# AQM2a.net
KiCad netlist of a schematic drawn in EasyEDA Pro
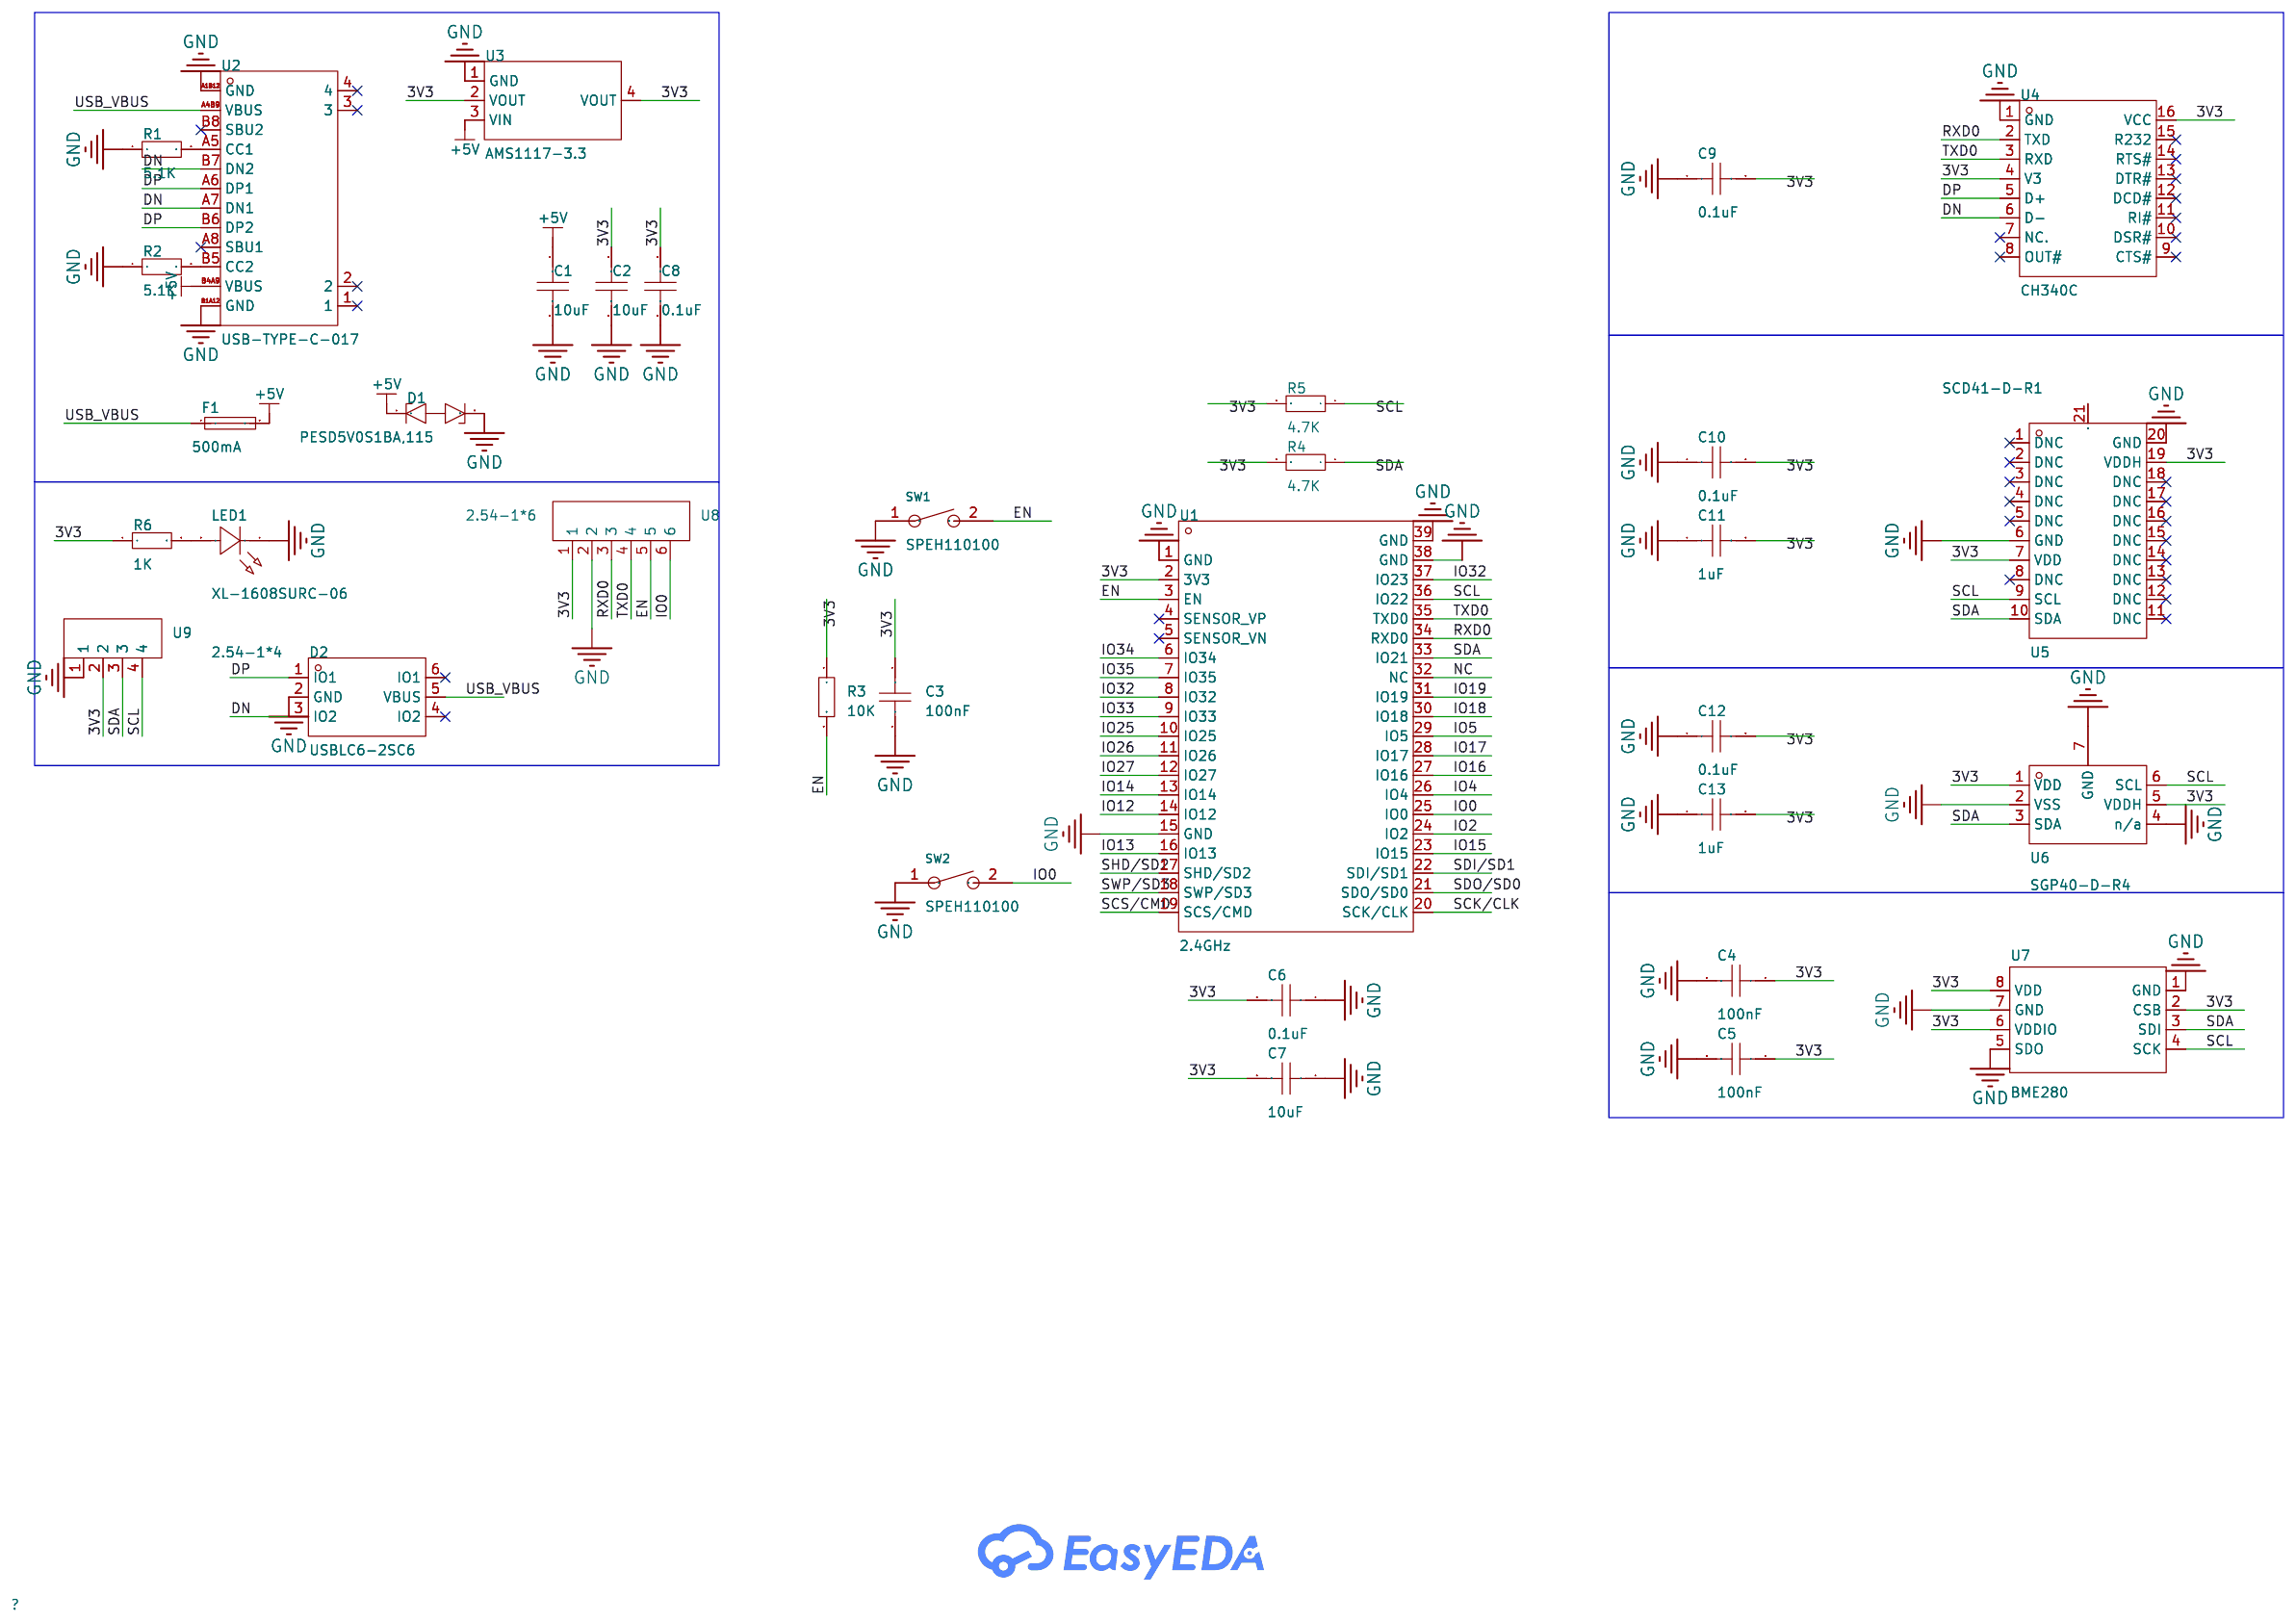
[diagram p0: schematic sheet]

(export (version "E")
  (design (tool "Eeschema 10.0.6"))
  (components
    (comp (ref "C1")
      (value "10uF")
      (footprint "easyedapro:C0603")
      (libsource (lib "easyedapro") (part "CAP"))
    )
    (comp (ref "C2")
      (value "10uF")
      (footprint "easyedapro:C0603")
      (libsource (lib "easyedapro") (part "CAP"))
    )
    (comp (ref "C3")
      (value "100nF")
      (footprint "easyedapro:C0603")
      (libsource (lib "easyedapro") (part "CAP"))
    )
    (comp (ref "C4")
      (value "100nF")
      (footprint "easyedapro:C0603")
      (libsource (lib "easyedapro") (part "CAP"))
    )
    (comp (ref "C5")
      (value "100nF")
      (footprint "easyedapro:C0603")
      (libsource (lib "easyedapro") (part "CAP"))
    )
    (comp (ref "C6")
      (value "0.1uF")
      (footprint "easyedapro:C0603")
      (libsource (lib "easyedapro") (part "CAP"))
    )
    (comp (ref "C7")
      (value "10uF")
      (footprint "easyedapro:C0603")
      (libsource (lib "easyedapro") (part "CAP"))
    )
    (comp (ref "C8")
      (value "0.1uF")
      (footprint "easyedapro:C0603")
      (libsource (lib "easyedapro") (part "CAP"))
    )
    (comp (ref "C9")
      (value "0.1uF")
      (footprint "easyedapro:C0603")
      (libsource (lib "easyedapro") (part "CAP"))
    )
    (comp (ref "C10")
      (value "0.1uF")
      (footprint "easyedapro:C0603")
      (libsource (lib "easyedapro") (part "CAP"))
    )
    (comp (ref "C11")
      (value "1uF")
      (footprint "easyedapro:C0603")
      (libsource (lib "easyedapro") (part "CAP"))
    )
    (comp (ref "C12")
      (value "0.1uF")
      (footprint "easyedapro:C0603")
      (libsource (lib "easyedapro") (part "CAP"))
    )
    (comp (ref "C13")
      (value "1uF")
      (footprint "easyedapro:C0603")
      (libsource (lib "easyedapro") (part "CAP"))
    )
    (comp (ref "D1")
      (value "PESD5V0S1BA,115")
      (footprint "easyedapro:SOD-323_L1.7-W1.3-LS2.5-BI")
      (fields (field (name "Manufacturer") "Nexperia(安世)"))
      (libsource (lib "easyedapro") (part "PESD5V0S1BA,115"))
    )
    (comp (ref "D2")
      (value "USBLC6-2SC6")
      (footprint "easyedapro:SOT-23-6_L2.9-W1.6-P0.95-LS2.8-BL")
      (fields (field (name "Manufacturer") "TECH PUBLIC(台舟)"))
      (libsource (lib "easyedapro") (part "USBLC6-2SC6_C2827654"))
    )
    (comp (ref "F1")
      (value "500mA")
      (footprint "easyedapro:F1812")
      (fields (field (name "Manufacturer") "PTTC(聚鼎)"))
      (libsource (lib "easyedapro") (part "SMD1812P260TF/16_C438899"))
    )
    (comp (ref "LED1")
      (value "XL-1608SURC-06")
      (footprint "easyedapro:LED0603-RD_RED")
      (fields (field (name "Manufacturer") "XINGLIGHT(成兴光)"))
      (libsource (lib "easyedapro") (part "XL-1608SURC-06"))
    )
    (comp (ref "R1")
      (value "5.1K")
      (footprint "easyedapro:R0603")
      (libsource (lib "easyedapro") (part "Res"))
    )
    (comp (ref "R2")
      (value "5.1K")
      (footprint "easyedapro:R0603")
      (libsource (lib "easyedapro") (part "Res"))
    )
    (comp (ref "R3") (value "10K") (footprint "easyedapro:R0603") (libsource (lib "easyedapro") (part "Res")))
    (comp (ref "R4")
      (value "4.7K")
      (footprint "easyedapro:R0603")
      (libsource (lib "easyedapro") (part "Res"))
    )
    (comp (ref "R5")
      (value "4.7K")
      (footprint "easyedapro:R0603")
      (libsource (lib "easyedapro") (part "Res"))
    )
    (comp (ref "R6") (value "1K") (footprint "easyedapro:R0603") (libsource (lib "easyedapro") (part "Res")))
    (comp (ref "SW1")
      (value "SPEH110100")
      (footprint "easyedapro:SW-SMD_L6.0-W6.0-LS6.6")
      (fields (field (name "Manufacturer") "ALPSALPINE(阿尔卑斯阿尔派)"))
      (libsource (lib "easyedapro") (part "SPEH110100"))
    )
    (comp (ref "SW2")
      (value "SPEH110100")
      (footprint "easyedapro:SW-SMD_L6.0-W6.0-LS6.6")
      (fields (field (name "Manufacturer") "ALPSALPINE(阿尔卑斯阿尔派)"))
      (libsource (lib "easyedapro") (part "SPEH110100"))
    )
    (comp (ref "U1")
      (value "2.4GHz")
      (footprint "easyedapro:WIFIM-SMD_ESP32-WROOM-32-N4")
      (fields
        (field (name "Manufacturer Part") "ESP32-WROOM-32-N4")
        (field (name "Manufacturer") "ESPRESSIF(乐鑫)")
      )
      (libsource (lib "easyedapro") (part "ESP32-WROOM-32"))
    )
    (comp (ref "U2")
      (value "USB-TYPE-C-017")
      (footprint "easyedapro:USB-TYPE-C-SMD_C9900008089")
      (fields (field (name "Manufacturer") "DEALON(德艺隆)"))
      (libsource (lib "easyedapro") (part "USB-TYPE-C-017"))
    )
    (comp (ref "U3")
      (value "AMS1117-3.3")
      (footprint "easyedapro:SOT-223-3_L6.5-W3.4-P2.30-LS7.0-BR")
      (fields (field (name "Manufacturer") "AMS"))
      (libsource (lib "easyedapro") (part "AMS1117-3.3"))
    )
    (comp (ref "U4")
      (value "CH340C")
      (footprint "easyedapro:SOP-16_L10.0-W3.9-P1.27-LS6.0-BL")
      (fields (field (name "Manufacturer") "WCH(南京沁恒)"))
      (libsource (lib "easyedapro") (part "CH340C"))
    )
    (comp (ref "U5")
      (value "SCD41-D-R1")
      (footprint "easyedapro:SENSOR-SMD_SCD41-D-R1")
      (fields (field (name "Manufacturer") "Sensirion(瑞士盛思锐)"))
      (libsource (lib "easyedapro") (part "SCD41-D-R1"))
    )
    (comp (ref "U6")
      (value "SGP40-D-R4")
      (footprint "easyedapro:DFN-6_L2.4-W2.4-P0.80-TL-EP")
      (fields (field (name "Manufacturer") "Sensirion(瑞士盛思锐)"))
      (libsource (lib "easyedapro") (part "SGP40-D-R4"))
    )
    (comp (ref "U7")
      (value "BME280")
      (footprint "easyedapro:LGA-8_BME280_BL")
      (fields (field (name "Manufacturer") "Bosch(博世)"))
      (libsource (lib "easyedapro") (part "BME280"))
    )
    (comp (ref "U8")
      (value "2.54-1*6")
      (footprint "easyedapro:HDR-TH_6P-P2.54-V-M")
      (fields (field (name "Manufacturer") "ZHOURI(洲日)"))
      (libsource (lib "easyedapro") (part "2.54-1*6"))
    )
    (comp (ref "U9")
      (value "2.54-1*4")
      (footprint "easyedapro:HDR-TH_4P-P2.54-V-M-1")
      (fields (field (name "Manufacturer") "ZHOURI(洲日)"))
      (libsource (lib "easyedapro") (part "2.54-1*4"))
    )
  )
  (nets
    (net (code "1") (name "+5V") (class "Default")
      (node (ref "C1") (pin "1") (pinfunction "1_1") (pintype "input"))
      (node (ref "D1") (pin "1") (pinfunction "1_1") (pintype "unspecified"))
      (node (ref "F1") (pin "2") (pinfunction "2_2") (pintype "unspecified"))
      (node (ref "U2") (pin "B4A9") (pinfunction "VBUS_B4A9") (pintype "unspecified"))
      (node (ref "U3") (pin "3") (pinfunction "VIN_3") (pintype "unspecified"))
    )
    (net (code "2") (name "/3V3") (class "Default")
      (node (ref "C10") (pin "2") (pinfunction "2_2") (pintype "input"))
      (node (ref "C11") (pin "2") (pinfunction "2_2") (pintype "input"))
      (node (ref "C12") (pin "2") (pinfunction "2_2") (pintype "input"))
      (node (ref "C13") (pin "2") (pinfunction "2_2") (pintype "input"))
      (node (ref "C2") (pin "1") (pinfunction "1_1") (pintype "input"))
      (node (ref "C3") (pin "1") (pinfunction "1_1") (pintype "input"))
      (node (ref "C4") (pin "1") (pinfunction "1_1") (pintype "input"))
      (node (ref "C5") (pin "1") (pinfunction "1_1") (pintype "input"))
      (node (ref "C6") (pin "2") (pinfunction "2_2") (pintype "input"))
      (node (ref "C7") (pin "2") (pinfunction "2_2") (pintype "input"))
      (node (ref "C8") (pin "1") (pinfunction "1_1") (pintype "input"))
      (node (ref "C9") (pin "2") (pinfunction "2_2") (pintype "input"))
      (node (ref "R3") (pin "1") (pinfunction "1_1") (pintype "input"))
      (node (ref "R4") (pin "2") (pinfunction "2_2") (pintype "input"))
      (node (ref "R5") (pin "2") (pinfunction "2_2") (pintype "input"))
      (node (ref "R6") (pin "1") (pinfunction "1_1") (pintype "input"))
      (node (ref "U1") (pin "2") (pinfunction "3V3_2") (pintype "unspecified"))
      (node (ref "U3") (pin "2") (pinfunction "VOUT_2") (pintype "unspecified"))
      (node (ref "U3") (pin "4") (pinfunction "VOUT_4") (pintype "unspecified"))
      (node (ref "U4") (pin "16") (pinfunction "VCC_16") (pintype "unspecified"))
      (node (ref "U4") (pin "4") (pinfunction "V3_4") (pintype "unspecified"))
      (node (ref "U5") (pin "19") (pinfunction "VDDH_19") (pintype "unspecified"))
      (node (ref "U5") (pin "7") (pinfunction "VDD_7") (pintype "unspecified"))
      (node (ref "U6") (pin "1") (pinfunction "VDD_1") (pintype "unspecified"))
      (node (ref "U6") (pin "5") (pinfunction "VDDH_5") (pintype "unspecified"))
      (node (ref "U7") (pin "2") (pinfunction "CSB_2") (pintype "unspecified"))
      (node (ref "U7") (pin "6") (pinfunction "VDDIO_6") (pintype "unspecified"))
      (node (ref "U7") (pin "8") (pinfunction "VDD_8") (pintype "unspecified"))
      (node (ref "U8") (pin "1") (pinfunction "1_1") (pintype "unspecified"))
      (node (ref "U9") (pin "2") (pinfunction "2_2") (pintype "unspecified"))
    )
    (net (code "3") (name "/DN") (class "Default")
      (node (ref "D2") (pin "3") (pinfunction "IO2_3") (pintype "unspecified"))
      (node (ref "U2") (pin "A7") (pinfunction "DN1_A7") (pintype "unspecified"))
      (node (ref "U2") (pin "B7") (pinfunction "DN2_B7") (pintype "unspecified"))
      (node (ref "U4") (pin "6") (pinfunction "D-_6") (pintype "unspecified"))
    )
    (net (code "4") (name "/DP") (class "Default")
      (node (ref "D2") (pin "1") (pinfunction "IO1_1") (pintype "unspecified"))
      (node (ref "U2") (pin "A6") (pinfunction "DP1_A6") (pintype "unspecified"))
      (node (ref "U2") (pin "B6") (pinfunction "DP2_B6") (pintype "unspecified"))
      (node (ref "U4") (pin "5") (pinfunction "D+_5") (pintype "unspecified"))
    )
    (net (code "5") (name "/EN") (class "Default")
      (node (ref "R3") (pin "2") (pinfunction "2_2") (pintype "input"))
      (node (ref "SW1") (pin "2") (pinfunction "2_2") (pintype "input"))
      (node (ref "U1") (pin "3") (pinfunction "EN_3") (pintype "unspecified"))
      (node (ref "U8") (pin "5") (pinfunction "5_5") (pintype "unspecified"))
    )
    (net (code "6") (name "/IO0") (class "Default")
      (node (ref "SW2") (pin "2") (pinfunction "2_2") (pintype "input"))
      (node (ref "U1") (pin "25") (pinfunction "IO0_25") (pintype "unspecified"))
      (node (ref "U8") (pin "6") (pinfunction "6_6") (pintype "unspecified"))
    )
    (net (code "7") (name "/IO2") (class "Default")
      (node (ref "U1") (pin "24") (pinfunction "IO2_24") (pintype "unspecified"))
    )
    (net (code "8") (name "/IO4") (class "Default")
      (node (ref "U1") (pin "26") (pinfunction "IO4_26") (pintype "unspecified"))
    )
    (net (code "9") (name "/IO5") (class "Default")
      (node (ref "U1") (pin "29") (pinfunction "IO5_29") (pintype "unspecified"))
    )
    (net (code "10") (name "/IO12") (class "Default")
      (node (ref "U1") (pin "14") (pinfunction "IO12_14") (pintype "unspecified"))
    )
    (net (code "11") (name "/IO13") (class "Default")
      (node (ref "U1") (pin "16") (pinfunction "IO13_16") (pintype "unspecified"))
    )
    (net (code "12") (name "/IO14") (class "Default")
      (node (ref "U1") (pin "13") (pinfunction "IO14_13") (pintype "unspecified"))
    )
    (net (code "13") (name "/IO15") (class "Default")
      (node (ref "U1") (pin "23") (pinfunction "IO15_23") (pintype "unspecified"))
    )
    (net (code "14") (name "/IO16") (class "Default")
      (node (ref "U1") (pin "27") (pinfunction "IO16_27") (pintype "unspecified"))
    )
    (net (code "15") (name "/IO17") (class "Default")
      (node (ref "U1") (pin "28") (pinfunction "IO17_28") (pintype "unspecified"))
    )
    (net (code "16") (name "/IO18") (class "Default")
      (node (ref "U1") (pin "30") (pinfunction "IO18_30") (pintype "unspecified"))
    )
    (net (code "17") (name "/IO19") (class "Default")
      (node (ref "U1") (pin "31") (pinfunction "IO19_31") (pintype "unspecified"))
    )
    (net (code "18") (name "/IO25") (class "Default")
      (node (ref "U1") (pin "10") (pinfunction "IO25_10") (pintype "unspecified"))
    )
    (net (code "19") (name "/IO26") (class "Default")
      (node (ref "U1") (pin "11") (pinfunction "IO26_11") (pintype "unspecified"))
    )
    (net (code "20") (name "/IO27") (class "Default")
      (node (ref "U1") (pin "12") (pinfunction "IO27_12") (pintype "unspecified"))
    )
    (net (code "21") (name "/IO32") (class "Default")
      (node (ref "U1") (pin "37") (pinfunction "IO23_37") (pintype "unspecified"))
      (node (ref "U1") (pin "8") (pinfunction "IO32_8") (pintype "unspecified"))
    )
    (net (code "22") (name "/IO33") (class "Default")
      (node (ref "U1") (pin "9") (pinfunction "IO33_9") (pintype "unspecified"))
    )
    (net (code "23") (name "/IO34") (class "Default")
      (node (ref "U1") (pin "6") (pinfunction "IO34_6") (pintype "unspecified"))
    )
    (net (code "24") (name "/IO35") (class "Default")
      (node (ref "U1") (pin "7") (pinfunction "IO35_7") (pintype "unspecified"))
    )
    (net (code "25") (name "/NC") (class "Default")
      (node (ref "U1") (pin "32") (pinfunction "NC_32") (pintype "unspecified"))
    )
    (net (code "26") (name "/RXD0") (class "Default")
      (node (ref "U1") (pin "34") (pinfunction "RXD0_34") (pintype "unspecified"))
      (node (ref "U4") (pin "2") (pinfunction "TXD_2") (pintype "unspecified"))
      (node (ref "U8") (pin "3") (pinfunction "3_3") (pintype "unspecified"))
    )
    (net (code "27") (name "/SCK{slash}CLK") (class "Default")
      (node (ref "U1") (pin "20") (pinfunction "SCK/CLK_20") (pintype "unspecified"))
    )
    (net (code "28") (name "/SCL") (class "Default")
      (node (ref "R5") (pin "1") (pinfunction "1_1") (pintype "input"))
      (node (ref "U1") (pin "36") (pinfunction "IO22_36") (pintype "unspecified"))
      (node (ref "U5") (pin "9") (pinfunction "SCL_9") (pintype "unspecified"))
      (node (ref "U6") (pin "6") (pinfunction "SCL_6") (pintype "unspecified"))
      (node (ref "U7") (pin "4") (pinfunction "SCK_4") (pintype "unspecified"))
      (node (ref "U9") (pin "4") (pinfunction "4_4") (pintype "unspecified"))
    )
    (net (code "29") (name "/SCS{slash}CMD") (class "Default")
      (node (ref "U1") (pin "19") (pinfunction "SCS/CMD_19") (pintype "unspecified"))
    )
    (net (code "30") (name "/SDA") (class "Default")
      (node (ref "R4") (pin "1") (pinfunction "1_1") (pintype "input"))
      (node (ref "U1") (pin "33") (pinfunction "IO21_33") (pintype "unspecified"))
      (node (ref "U5") (pin "10") (pinfunction "SDA_10") (pintype "unspecified"))
      (node (ref "U6") (pin "3") (pinfunction "SDA_3") (pintype "unspecified"))
      (node (ref "U7") (pin "3") (pinfunction "SDI_3") (pintype "unspecified"))
      (node (ref "U9") (pin "3") (pinfunction "3_3") (pintype "unspecified"))
    )
    (net (code "31") (name "/SDI{slash}SD1") (class "Default")
      (node (ref "U1") (pin "22") (pinfunction "SDI/SD1_22") (pintype "unspecified"))
    )
    (net (code "32") (name "/SDO{slash}SD0") (class "Default")
      (node (ref "U1") (pin "21") (pinfunction "SDO/SD0_21") (pintype "unspecified"))
    )
    (net (code "33") (name "/SHD{slash}SD2") (class "Default")
      (node (ref "U1") (pin "17") (pinfunction "SHD/SD2_17") (pintype "unspecified"))
    )
    (net (code "34") (name "/SWP{slash}SD3") (class "Default")
      (node (ref "U1") (pin "18") (pinfunction "SWP/SD3_18") (pintype "unspecified"))
    )
    (net (code "35") (name "/TXD0") (class "Default")
      (node (ref "U1") (pin "35") (pinfunction "TXD0_35") (pintype "unspecified"))
      (node (ref "U4") (pin "3") (pinfunction "RXD_3") (pintype "unspecified"))
      (node (ref "U8") (pin "4") (pinfunction "4_4") (pintype "unspecified"))
    )
    (net (code "36") (name "/USB_VBUS") (class "Default")
      (node (ref "D2") (pin "5") (pinfunction "VBUS_5") (pintype "unspecified"))
      (node (ref "F1") (pin "1") (pinfunction "1_1") (pintype "unspecified"))
      (node (ref "U2") (pin "A4B9") (pinfunction "VBUS_A4B9") (pintype "unspecified"))
    )
    (net (code "37") (name "GND") (class "Default")
      (node (ref "C1") (pin "2") (pinfunction "2_2") (pintype "input"))
      (node (ref "C10") (pin "1") (pinfunction "1_1") (pintype "input"))
      (node (ref "C11") (pin "1") (pinfunction "1_1") (pintype "input"))
      (node (ref "C12") (pin "1") (pinfunction "1_1") (pintype "input"))
      (node (ref "C13") (pin "1") (pinfunction "1_1") (pintype "input"))
      (node (ref "C2") (pin "2") (pinfunction "2_2") (pintype "input"))
      (node (ref "C3") (pin "2") (pinfunction "2_2") (pintype "input"))
      (node (ref "C4") (pin "2") (pinfunction "2_2") (pintype "input"))
      (node (ref "C5") (pin "2") (pinfunction "2_2") (pintype "input"))
      (node (ref "C6") (pin "1") (pinfunction "1_1") (pintype "input"))
      (node (ref "C7") (pin "1") (pinfunction "1_1") (pintype "input"))
      (node (ref "C8") (pin "2") (pinfunction "2_2") (pintype "input"))
      (node (ref "C9") (pin "1") (pinfunction "1_1") (pintype "input"))
      (node (ref "D1") (pin "2") (pinfunction "2_2") (pintype "unspecified"))
      (node (ref "D2") (pin "2") (pinfunction "GND_2") (pintype "unspecified"))
      (node (ref "LED1") (pin "1") (pinfunction "K_1") (pintype "unspecified"))
      (node (ref "R1") (pin "1") (pinfunction "1_1") (pintype "input"))
      (node (ref "R2") (pin "1") (pinfunction "1_1") (pintype "input"))
      (node (ref "SW1") (pin "1") (pinfunction "1_1") (pintype "input"))
      (node (ref "SW2") (pin "1") (pinfunction "1_1") (pintype "input"))
      (node (ref "U1") (pin "1") (pinfunction "GND_1") (pintype "unspecified"))
      (node (ref "U1") (pin "15") (pinfunction "GND_15") (pintype "unspecified"))
      (node (ref "U1") (pin "38") (pinfunction "GND_38") (pintype "unspecified"))
      (node (ref "U1") (pin "39") (pinfunction "GND_39") (pintype "unspecified"))
      (node (ref "U2") (pin "A1B12") (pinfunction "GND_A1B12") (pintype "unspecified"))
      (node (ref "U2") (pin "B1A12") (pinfunction "GND_B1A12") (pintype "unspecified"))
      (node (ref "U3") (pin "1") (pinfunction "GND_1") (pintype "unspecified"))
      (node (ref "U4") (pin "1") (pinfunction "GND_1") (pintype "unspecified"))
      (node (ref "U5") (pin "20") (pinfunction "GND_20") (pintype "unspecified"))
      (node (ref "U5") (pin "6") (pinfunction "GND_6") (pintype "unspecified"))
      (node (ref "U6") (pin "2") (pinfunction "VSS_2") (pintype "unspecified"))
      (node (ref "U6") (pin "4") (pinfunction "n/a_4") (pintype "unspecified"))
      (node (ref "U6") (pin "7") (pinfunction "GND_7") (pintype "unspecified"))
      (node (ref "U7") (pin "1") (pinfunction "GND_1") (pintype "unspecified"))
      (node (ref "U7") (pin "5") (pinfunction "SDO_5") (pintype "unspecified"))
      (node (ref "U7") (pin "7") (pinfunction "GND_7") (pintype "unspecified"))
      (node (ref "U8") (pin "2") (pinfunction "2_2") (pintype "unspecified"))
      (node (ref "U9") (pin "1") (pinfunction "1_1") (pintype "unspecified"))
    )
    (net (code "38") (name "Net-(LED1-A)") (class "Default")
      (node (ref "LED1") (pin "2") (pinfunction "A_2") (pintype "unspecified"))
      (node (ref "R6") (pin "2") (pinfunction "2_2") (pintype "input"))
    )
    (net (code "39") (name "Net-(U2-CC1)") (class "Default")
      (node (ref "R1") (pin "2") (pinfunction "2_2") (pintype "input"))
      (node (ref "U2") (pin "A5") (pinfunction "CC1_A5") (pintype "unspecified"))
    )
    (net (code "40") (name "Net-(U2-CC2)") (class "Default")
      (node (ref "R2") (pin "2") (pinfunction "2_2") (pintype "input"))
      (node (ref "U2") (pin "B5") (pinfunction "CC2_B5") (pintype "unspecified"))
    )
    (net (code "41") (name "unconnected-(D2-IO1-Pad6)") (class "Default")
      (node (ref "D2") (pin "6") (pinfunction "IO1_6") (pintype "unspecified+no_connect"))
    )
    (net (code "42") (name "unconnected-(D2-IO2-Pad4)") (class "Default")
      (node (ref "D2") (pin "4") (pinfunction "IO2_4") (pintype "unspecified+no_connect"))
    )
    (net (code "43") (name "unconnected-(U1-SENSOR_VN-Pad5)") (class "Default")
      (node (ref "U1") (pin "5") (pinfunction "SENSOR_VN_5") (pintype "unspecified+no_connect"))
    )
    (net (code "44") (name "unconnected-(U1-SENSOR_VP-Pad4)") (class "Default")
      (node (ref "U1") (pin "4") (pinfunction "SENSOR_VP_4") (pintype "unspecified+no_connect"))
    )
    (net (code "45") (name "unconnected-(U2-Pad1)") (class "Default")
      (node (ref "U2") (pin "1") (pinfunction "1_1") (pintype "unspecified+no_connect"))
    )
    (net (code "46") (name "unconnected-(U2-Pad2)") (class "Default")
      (node (ref "U2") (pin "2") (pinfunction "2_2") (pintype "unspecified+no_connect"))
    )
    (net (code "47") (name "unconnected-(U2-Pad3)") (class "Default")
      (node (ref "U2") (pin "3") (pinfunction "3_3") (pintype "unspecified+no_connect"))
    )
    (net (code "48") (name "unconnected-(U2-Pad4)") (class "Default")
      (node (ref "U2") (pin "4") (pinfunction "4_4") (pintype "unspecified+no_connect"))
    )
    (net (code "49") (name "unconnected-(U2-SBU1-PadA8)") (class "Default")
      (node (ref "U2") (pin "A8") (pinfunction "SBU1_A8") (pintype "unspecified+no_connect"))
    )
    (net (code "50") (name "unconnected-(U2-SBU2-PadB8)") (class "Default")
      (node (ref "U2") (pin "B8") (pinfunction "SBU2_B8") (pintype "unspecified+no_connect"))
    )
    (net (code "51") (name "unconnected-(U4-CTS#-Pad9)") (class "Default")
      (node (ref "U4") (pin "9") (pinfunction "CTS#_9") (pintype "unspecified+no_connect"))
    )
    (net (code "52") (name "unconnected-(U4-DCD#-Pad12)") (class "Default")
      (node (ref "U4") (pin "12") (pinfunction "DCD#_12") (pintype "unspecified+no_connect"))
    )
    (net (code "53") (name "unconnected-(U4-DSR#-Pad10)") (class "Default")
      (node (ref "U4") (pin "10") (pinfunction "DSR#_10") (pintype "unspecified+no_connect"))
    )
    (net (code "54") (name "unconnected-(U4-DTR#-Pad13)") (class "Default")
      (node (ref "U4") (pin "13") (pinfunction "DTR#_13") (pintype "unspecified+no_connect"))
    )
    (net (code "55") (name "unconnected-(U4-NC.-Pad7)") (class "Default")
      (node (ref "U4") (pin "7") (pinfunction "NC._7") (pintype "unspecified+no_connect"))
    )
    (net (code "56") (name "unconnected-(U4-OUT#-Pad8)") (class "Default")
      (node (ref "U4") (pin "8") (pinfunction "OUT#_8") (pintype "unspecified+no_connect"))
    )
    (net (code "57") (name "unconnected-(U4-R232-Pad15)") (class "Default")
      (node (ref "U4") (pin "15") (pinfunction "R232_15") (pintype "unspecified+no_connect"))
    )
    (net (code "58") (name "unconnected-(U4-RI#-Pad11)") (class "Default")
      (node (ref "U4") (pin "11") (pinfunction "RI#_11") (pintype "unspecified+no_connect"))
    )
    (net (code "59") (name "unconnected-(U4-RTS#-Pad14)") (class "Default")
      (node (ref "U4") (pin "14") (pinfunction "RTS#_14") (pintype "unspecified+no_connect"))
    )
    (net (code "60") (name "unconnected-(U5-DNC-Pad1)") (class "Default")
      (node (ref "U5") (pin "1") (pinfunction "DNC_1") (pintype "unspecified+no_connect"))
    )
    (net (code "61") (name "unconnected-(U5-DNC-Pad2)") (class "Default")
      (node (ref "U5") (pin "2") (pinfunction "DNC_2") (pintype "unspecified+no_connect"))
    )
    (net (code "62") (name "unconnected-(U5-DNC-Pad3)") (class "Default")
      (node (ref "U5") (pin "3") (pinfunction "DNC_3") (pintype "unspecified+no_connect"))
    )
    (net (code "63") (name "unconnected-(U5-DNC-Pad4)") (class "Default")
      (node (ref "U5") (pin "4") (pinfunction "DNC_4") (pintype "unspecified+no_connect"))
    )
    (net (code "64") (name "unconnected-(U5-DNC-Pad5)") (class "Default")
      (node (ref "U5") (pin "5") (pinfunction "DNC_5") (pintype "unspecified+no_connect"))
    )
    (net (code "65") (name "unconnected-(U5-DNC-Pad8)") (class "Default")
      (node (ref "U5") (pin "8") (pinfunction "DNC_8") (pintype "unspecified+no_connect"))
    )
    (net (code "66") (name "unconnected-(U5-DNC-Pad11)") (class "Default")
      (node (ref "U5") (pin "11") (pinfunction "DNC_11") (pintype "unspecified+no_connect"))
    )
    (net (code "67") (name "unconnected-(U5-DNC-Pad12)") (class "Default")
      (node (ref "U5") (pin "12") (pinfunction "DNC_12") (pintype "unspecified+no_connect"))
    )
    (net (code "68") (name "unconnected-(U5-DNC-Pad13)") (class "Default")
      (node (ref "U5") (pin "13") (pinfunction "DNC_13") (pintype "unspecified+no_connect"))
    )
    (net (code "69") (name "unconnected-(U5-DNC-Pad14)") (class "Default")
      (node (ref "U5") (pin "14") (pinfunction "DNC_14") (pintype "unspecified+no_connect"))
    )
    (net (code "70") (name "unconnected-(U5-DNC-Pad15)") (class "Default")
      (node (ref "U5") (pin "15") (pinfunction "DNC_15") (pintype "unspecified+no_connect"))
    )
    (net (code "71") (name "unconnected-(U5-DNC-Pad16)") (class "Default")
      (node (ref "U5") (pin "16") (pinfunction "DNC_16") (pintype "unspecified+no_connect"))
    )
    (net (code "72") (name "unconnected-(U5-DNC-Pad17)") (class "Default")
      (node (ref "U5") (pin "17") (pinfunction "DNC_17") (pintype "unspecified+no_connect"))
    )
    (net (code "73") (name "unconnected-(U5-DNC-Pad18)") (class "Default")
      (node (ref "U5") (pin "18") (pinfunction "DNC_18") (pintype "unspecified+no_connect"))
    )
    (net (code "74") (name "unconnected-(U5-GND-Pad21)") (class "Default")
      (node (ref "U5") (pin "21") (pinfunction "GND_21") (pintype "unspecified"))
    )
  )
)
